# rj45-breakout-10_5_0.net
KiCad netlist of a schematic drawn in EAGLE
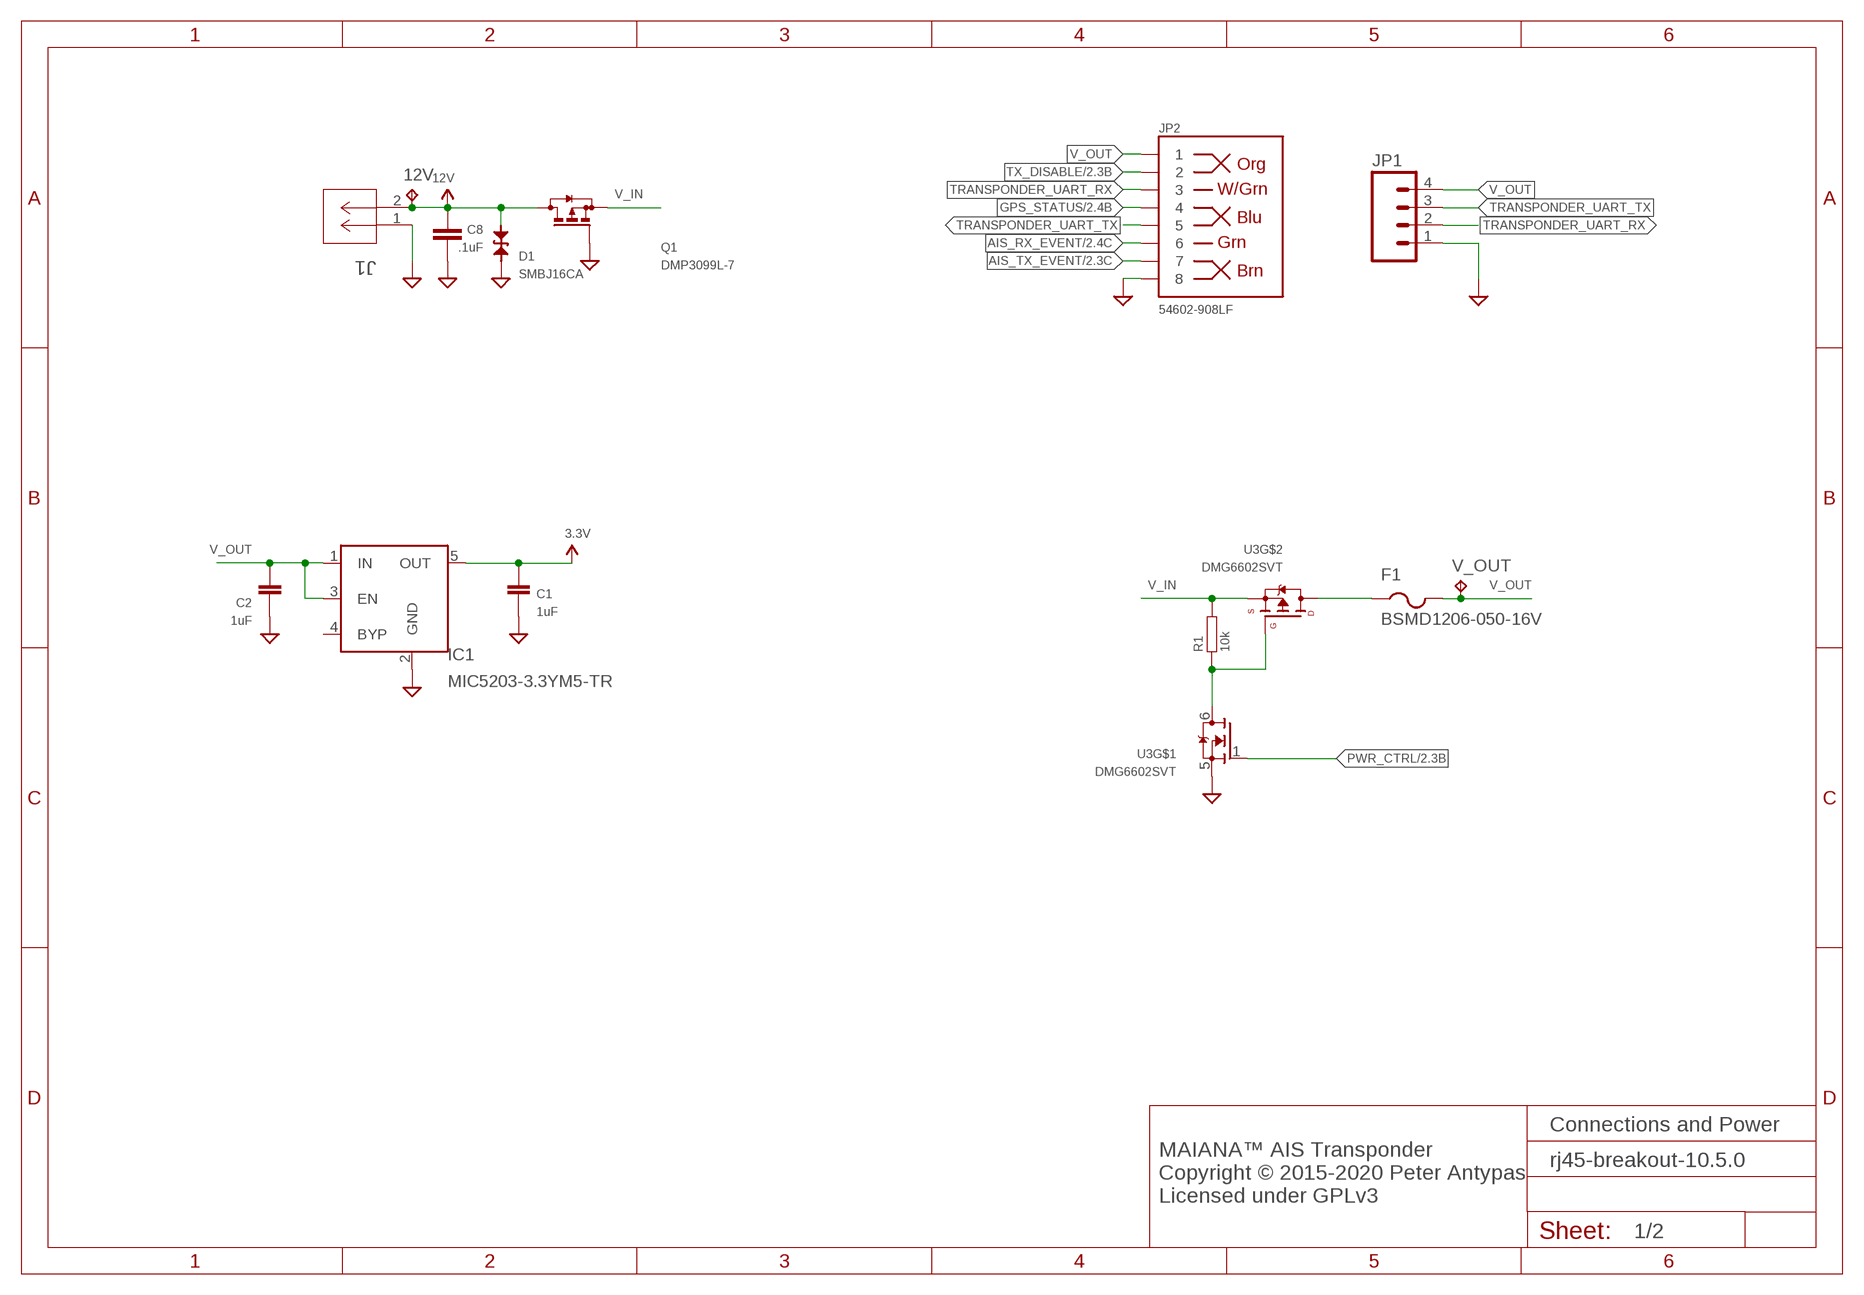
[diagram p0: schematic, sheet 1]
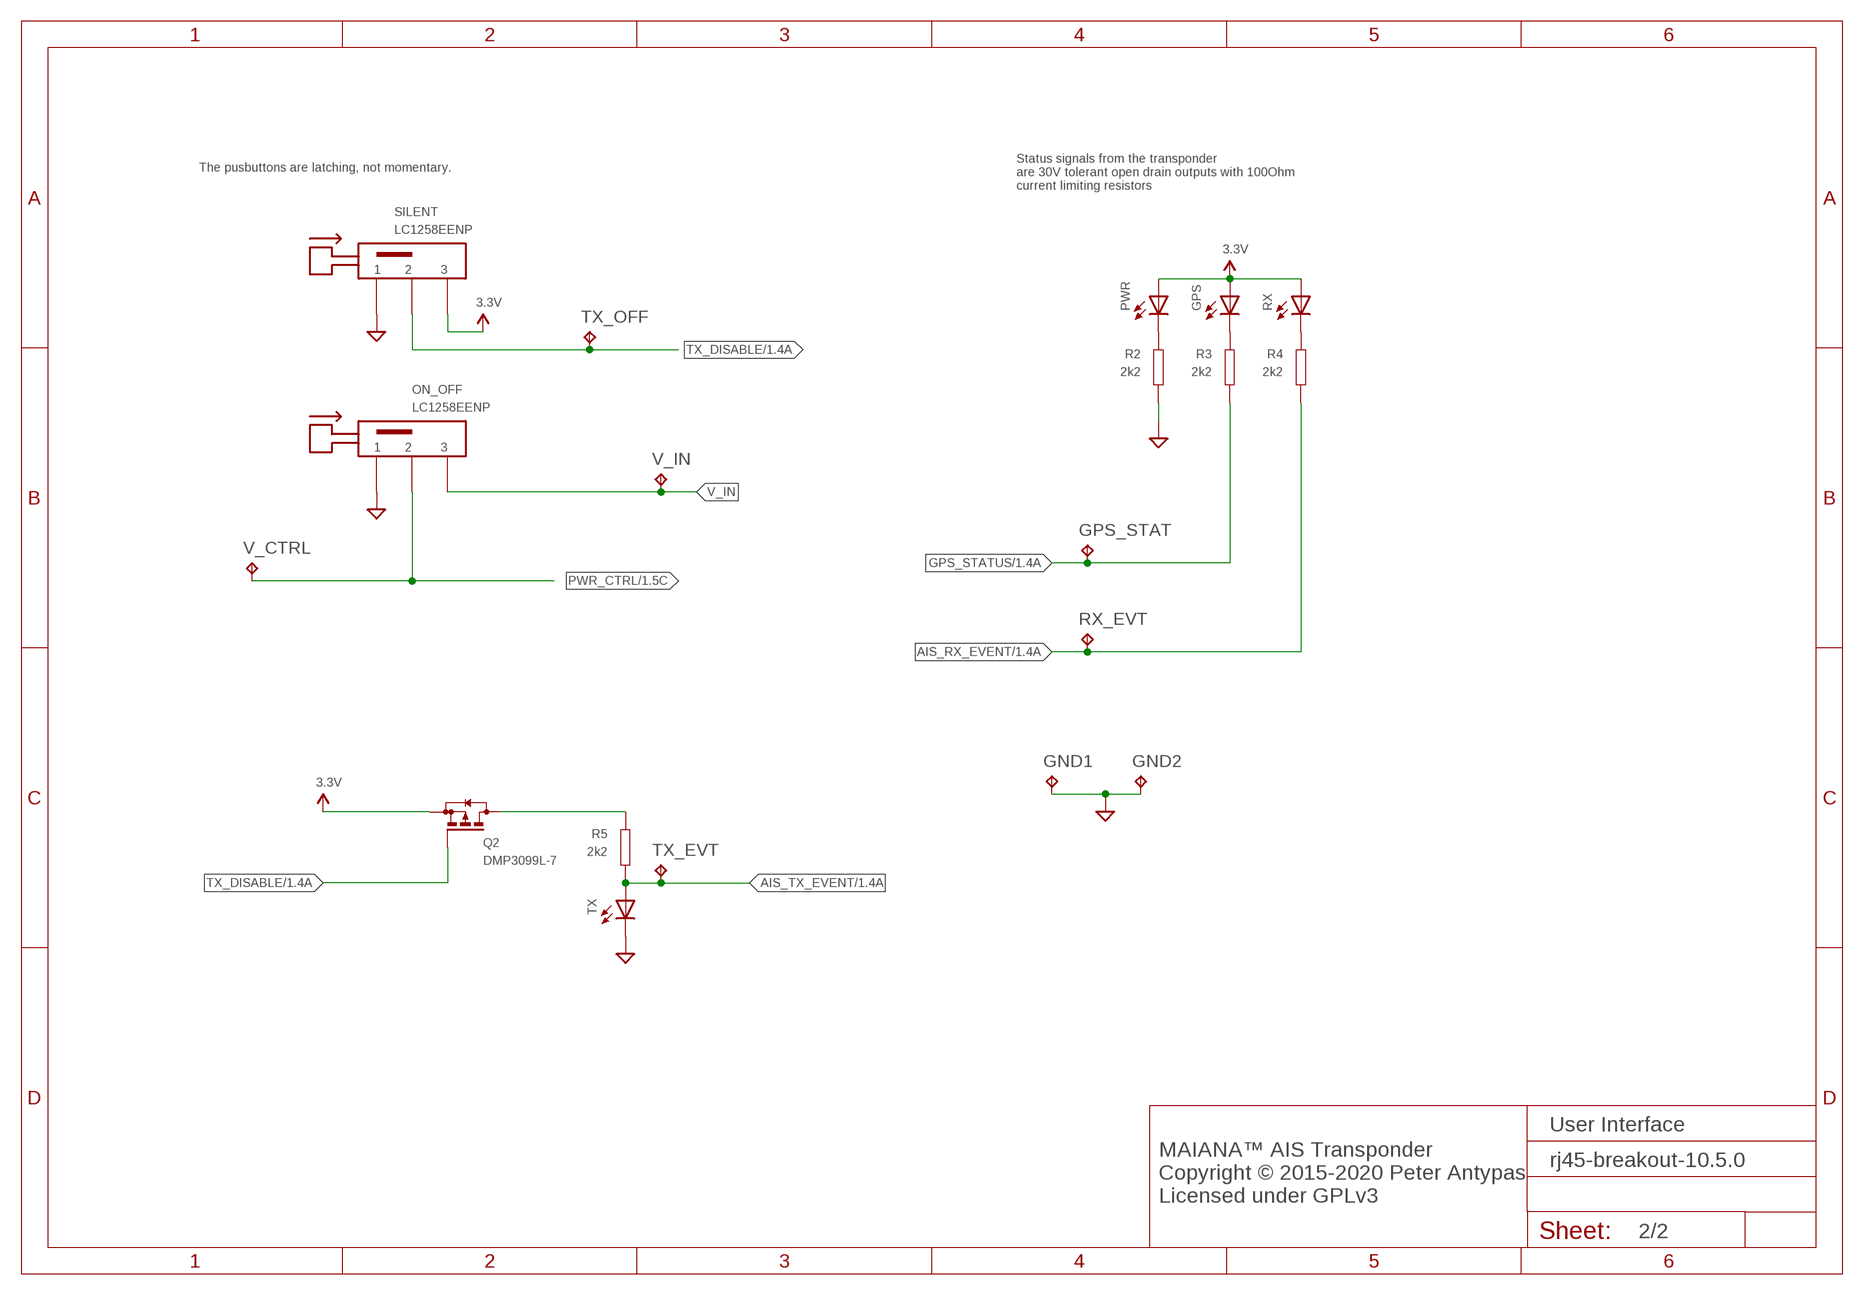
[diagram p1: schematic, sheet 2]

(export (version "E")
  (design (tool "Eeschema 10.0.6"))
  (components
    (comp (ref "GND1")
      (value "TPTP20R")
      (footprint "eagle-import:TP20R")
      (libsource (lib "eagle-import") (part "TPTP20R"))
    )
    (comp (ref "GND2")
      (value "TPTP20R")
      (footprint "eagle-import:TP20R")
      (libsource (lib "eagle-import") (part "TPTP20R"))
    )
    (comp (ref "GPS")
      (value "LEDCHIPLED_1206")
      (footprint "eagle-import:CHIPLED_1206")
      (libsource (lib "eagle-import") (part "LEDCHIPLED_1206"))
    )
    (comp (ref "GPS_STAT")
      (value "TPTP20R")
      (footprint "eagle-import:TP20R")
      (libsource (lib "eagle-import") (part "TPTP20R"))
    )
    (comp (ref "ON_OFF")
      (value "LC1258EENP")
      (footprint "eagle-import:LC1258XXNP")
      (libsource (lib "eagle-import") (part "LC1258XXNP"))
    )
    (comp (ref "PWR")
      (value "LEDCHIPLED_1206")
      (footprint "eagle-import:CHIPLED_1206")
      (libsource (lib "eagle-import") (part "LEDCHIPLED_1206"))
    )
    (comp (ref "Q2")
      (value "DMP3099L-7")
      (footprint "eagle-import:SOT23")
      (libsource (lib "eagle-import") (part "BSS84"))
    )
    (comp (ref "R2")
      (value "2k2")
      (footprint "eagle-import:0603")
      (libsource (lib "eagle-import") (part "RESISTOR0603"))
    )
    (comp (ref "R3")
      (value "2k2")
      (footprint "eagle-import:0603")
      (libsource (lib "eagle-import") (part "RESISTOR0603"))
    )
    (comp (ref "R4")
      (value "2k2")
      (footprint "eagle-import:0603")
      (libsource (lib "eagle-import") (part "RESISTOR0603"))
    )
    (comp (ref "R5")
      (value "2k2")
      (footprint "eagle-import:0603")
      (libsource (lib "eagle-import") (part "RESISTOR0603"))
    )
    (comp (ref "RX")
      (value "LEDCHIPLED_1206")
      (footprint "eagle-import:CHIPLED_1206")
      (libsource (lib "eagle-import") (part "LEDCHIPLED_1206"))
    )
    (comp (ref "RX_EVT")
      (value "TPTP20R")
      (footprint "eagle-import:TP20R")
      (libsource (lib "eagle-import") (part "TPTP20R"))
    )
    (comp (ref "SILENT")
      (value "LC1258EENP")
      (footprint "eagle-import:LC1258XXNP")
      (libsource (lib "eagle-import") (part "LC1258XXNP"))
    )
    (comp (ref "TX")
      (value "LEDCHIPLED_1206")
      (footprint "eagle-import:CHIPLED_1206")
      (libsource (lib "eagle-import") (part "LEDCHIPLED_1206"))
    )
    (comp (ref "TX_EVT")
      (value "TPTP20R")
      (footprint "eagle-import:TP20R")
      (libsource (lib "eagle-import") (part "TPTP20R"))
    )
    (comp (ref "TX_OFF")
      (value "TPTP20R")
      (footprint "eagle-import:TP20R")
      (libsource (lib "eagle-import") (part "TPTP20R"))
    )
    (comp (ref "V_CTRL")
      (value "TPTP20R")
      (footprint "eagle-import:TP20R")
      (libsource (lib "eagle-import") (part "TPTP20R"))
    )
    (comp (ref "V_IN")
      (value "TPTP20R")
      (footprint "eagle-import:TP20R")
      (libsource (lib "eagle-import") (part "TPTP20R"))
    )
    (comp (ref "12V")
      (value "TPTP20R")
      (footprint "eagle-import:TP20R")
      (libsource (lib "eagle-import") (part "TPTP20R"))
    )
    (comp (ref "C1")
      (value "1uF")
      (footprint "eagle-import:0603")
      (libsource (lib "eagle-import") (part "CAPACITOR0603"))
    )
    (comp (ref "C2")
      (value "1uF")
      (footprint "eagle-import:0603")
      (libsource (lib "eagle-import") (part "CAPACITOR0603"))
    )
    (comp (ref "C8")
      (value ".1uF")
      (footprint "eagle-import:0603-CAP")
      (fields (field (name "PARTNO") "GRM188R71E223KA01D"))
      (libsource (lib "eagle-import") (part "CAP0603-CAP"))
    )
    (comp (ref "D1")
      (value "SMBJ16CA")
      (footprint "eagle-import:SMB-BIDIR")
      (libsource (lib "eagle-import") (part "DIODE-TVS-BIDIRSMB"))
    )
    (comp (ref "F1")
      (value "BSMD1206-050-16V")
      (footprint "eagle-import:R1206")
      (libsource (lib "eagle-import") (part "PTCFUSE-1206"))
    )
    (comp (ref "IC1")
      (value "MIC5203-3.3YM5-TR")
      (footprint "eagle-import:SOT23-5")
      (libsource (lib "eagle-import") (part "MIC5219XX"))
    )
    (comp (ref "J1")
      (value "OSTVN02A150")
      (footprint "eagle-import:CONN_OSTVN02A150_OST")
      (fields (field (name "COPYRIGHT") "Copyright (C) 2018 Accelerated Designs. All rights reserved"))
      (libsource (lib "eagle-import") (part "OSTVN02A150"))
    )
    (comp (ref "JP1")
      (value "M04PTH")
      (footprint "eagle-import:1X04")
      (libsource (lib "eagle-import") (part "M04PTH"))
    )
    (comp (ref "JP2")
      (value "54602-908LF")
      (footprint "eagle-import:RJ45-8")
      (libsource (lib "eagle-import") (part "RJ45-8PTH"))
    )
    (comp (ref "Q1")
      (value "DMP3099L-7")
      (footprint "eagle-import:SOT23")
      (libsource (lib "eagle-import") (part "BSS84"))
    )
    (comp (ref "R1")
      (value "10k")
      (footprint "eagle-import:0603")
      (libsource (lib "eagle-import") (part "RESISTOR0603"))
    )
    (comp (ref "U3")
      (value "DMG6602SVT")
      (footprint "eagle-import:SOT23-6")
      (libsource (lib "eagle-import") (part "DMG6602SVT"))
    )
    (comp (ref "V_OUT")
      (value "TPTP20R")
      (footprint "eagle-import:TP20R")
      (libsource (lib "eagle-import") (part "TPTP20R"))
    )
  )
  (nets
    (net (code "1") (name "3.3V") (class "Default")
      (node (ref "C1") (pin "P$1") (pinfunction "1_P$1") (pintype "passive"))
      (node (ref "GPS") (pin "A") (pinfunction "A_A") (pintype "passive"))
      (node (ref "IC1") (pin "5") (pinfunction "OUT_5") (pintype "output"))
      (node (ref "PWR") (pin "A") (pinfunction "A_A") (pintype "passive"))
      (node (ref "Q2") (pin "2") (pinfunction "S_2") (pintype "passive"))
      (node (ref "RX") (pin "A") (pinfunction "A_A") (pintype "passive"))
      (node (ref "SILENT") (pin "P$3") (pinfunction "3_P$3") (pintype "bidirectional"))
    )
    (net (code "2") (name "12V") (class "Default")
      (node (ref "12V") (pin "TP") (pinfunction "TP_TP") (pintype "input"))
      (node (ref "C8") (pin "1") (pinfunction "1_1") (pintype "passive"))
      (node (ref "D1") (pin "A") (pinfunction "P$1_A") (pintype "bidirectional"))
      (node (ref "J1") (pin "2") (pinfunction "2_2") (pintype "passive"))
      (node (ref "Q1") (pin "3") (pinfunction "D_3") (pintype "passive"))
    )
    (net (code "3") (name "AIS_RX_EVENT") (class "Default")
      (node (ref "JP2") (pin "6") (pinfunction "6_6") (pintype "bidirectional"))
      (node (ref "R4") (pin "P$2") (pinfunction "P$2_P$2") (pintype "passive"))
      (node (ref "RX_EVT") (pin "TP") (pinfunction "TP_TP") (pintype "input"))
    )
    (net (code "4") (name "AIS_TX_EVENT") (class "Default")
      (node (ref "JP2") (pin "7") (pinfunction "7_7") (pintype "bidirectional"))
      (node (ref "R5") (pin "P$2") (pinfunction "P$2_P$2") (pintype "passive"))
      (node (ref "TX") (pin "A") (pinfunction "A_A") (pintype "passive"))
      (node (ref "TX_EVT") (pin "TP") (pinfunction "TP_TP") (pintype "input"))
    )
    (net (code "5") (name "GND") (class "Default")
      (node (ref "C1") (pin "P$2") (pinfunction "2_P$2") (pintype "passive"))
      (node (ref "C2") (pin "P$2") (pinfunction "2_P$2") (pintype "passive"))
      (node (ref "C8") (pin "2") (pinfunction "2_2") (pintype "passive"))
      (node (ref "D1") (pin "C") (pinfunction "P$2_C") (pintype "bidirectional"))
      (node (ref "GND1") (pin "TP") (pinfunction "TP_TP") (pintype "input"))
      (node (ref "GND2") (pin "TP") (pinfunction "TP_TP") (pintype "input"))
      (node (ref "IC1") (pin "2") (pinfunction "GND_2") (pintype "power_in"))
      (node (ref "J1") (pin "1") (pinfunction "1_1") (pintype "passive"))
      (node (ref "JP1") (pin "1") (pinfunction "1_1") (pintype "passive"))
      (node (ref "JP2") (pin "8") (pinfunction "8_8") (pintype "bidirectional"))
      (node (ref "ON_OFF") (pin "P$1") (pinfunction "1_P$1") (pintype "bidirectional"))
      (node (ref "Q1") (pin "1") (pinfunction "G_1") (pintype "passive"))
      (node (ref "R2") (pin "P$2") (pinfunction "P$2_P$2") (pintype "passive"))
      (node (ref "SILENT") (pin "P$1") (pinfunction "1_P$1") (pintype "bidirectional"))
      (node (ref "TX") (pin "C") (pinfunction "C_C") (pintype "passive"))
      (node (ref "U3") (pin "5") (pinfunction "S_5") (pintype "bidirectional"))
    )
    (net (code "6") (name "GPS_STATUS") (class "Default")
      (node (ref "GPS_STAT") (pin "TP") (pinfunction "TP_TP") (pintype "input"))
      (node (ref "JP2") (pin "4") (pinfunction "4_4") (pintype "bidirectional"))
      (node (ref "R3") (pin "P$2") (pinfunction "P$2_P$2") (pintype "passive"))
    )
    (net (code "7") (name "Net-(GPS-PadC)") (class "Default")
      (node (ref "GPS") (pin "C") (pinfunction "C_C") (pintype "passive"))
      (node (ref "R3") (pin "P$1") (pinfunction "P$1_P$1") (pintype "passive"))
    )
    (net (code "8") (name "Net-(PWR-PadC)") (class "Default")
      (node (ref "PWR") (pin "C") (pinfunction "C_C") (pintype "passive"))
      (node (ref "R2") (pin "P$1") (pinfunction "P$1_P$1") (pintype "passive"))
    )
    (net (code "9") (name "Net-(Q2-D)") (class "Default")
      (node (ref "Q2") (pin "3") (pinfunction "D_3") (pintype "passive"))
      (node (ref "R5") (pin "P$1") (pinfunction "P$1_P$1") (pintype "passive"))
    )
    (net (code "10") (name "Net-(R4-PadP$1)") (class "Default")
      (node (ref "R4") (pin "P$1") (pinfunction "P$1_P$1") (pintype "passive"))
      (node (ref "RX") (pin "C") (pinfunction "C_C") (pintype "passive"))
    )
    (net (code "11") (name "Net-(U3A-D)") (class "Default")
      (node (ref "R1") (pin "P$1") (pinfunction "P$1_P$1") (pintype "passive"))
      (node (ref "U3") (pin "3") (pinfunction "G_3") (pintype "passive"))
      (node (ref "U3") (pin "6") (pinfunction "D_6") (pintype "bidirectional"))
    )
    (net (code "12") (name "Net-(U3B-D)") (class "Default")
      (node (ref "F1") (pin "1") (pinfunction "1_1") (pintype "passive"))
      (node (ref "U3") (pin "4") (pinfunction "D_4") (pintype "passive"))
    )
    (net (code "13") (name "PWR_CTRL") (class "Default")
      (node (ref "ON_OFF") (pin "P$2") (pinfunction "2_P$2") (pintype "bidirectional"))
      (node (ref "U3") (pin "1") (pinfunction "G_1") (pintype "bidirectional"))
      (node (ref "V_CTRL") (pin "TP") (pinfunction "TP_TP") (pintype "input"))
    )
    (net (code "14") (name "TRANSPONDER_UART_RX") (class "Default")
      (node (ref "JP1") (pin "2") (pinfunction "2_2") (pintype "passive"))
      (node (ref "JP2") (pin "3") (pinfunction "3_3") (pintype "bidirectional"))
    )
    (net (code "15") (name "TRANSPONDER_UART_TX") (class "Default")
      (node (ref "JP1") (pin "3") (pinfunction "3_3") (pintype "passive"))
      (node (ref "JP2") (pin "5") (pinfunction "5_5") (pintype "bidirectional"))
    )
    (net (code "16") (name "TX_DISABLE") (class "Default")
      (node (ref "JP2") (pin "2") (pinfunction "2_2") (pintype "bidirectional"))
      (node (ref "Q2") (pin "1") (pinfunction "G_1") (pintype "passive"))
      (node (ref "SILENT") (pin "P$2") (pinfunction "2_P$2") (pintype "bidirectional"))
      (node (ref "TX_OFF") (pin "TP") (pinfunction "TP_TP") (pintype "input"))
    )
    (net (code "17") (name "V_IN") (class "Default")
      (node (ref "ON_OFF") (pin "P$3") (pinfunction "3_P$3") (pintype "bidirectional"))
      (node (ref "Q1") (pin "2") (pinfunction "S_2") (pintype "passive"))
      (node (ref "R1") (pin "P$2") (pinfunction "P$2_P$2") (pintype "passive"))
      (node (ref "U3") (pin "2") (pinfunction "S_2") (pintype "passive"))
      (node (ref "V_IN") (pin "TP") (pinfunction "TP_TP") (pintype "input"))
    )
    (net (code "18") (name "V_OUT") (class "Default")
      (node (ref "C2") (pin "P$1") (pinfunction "1_P$1") (pintype "passive"))
      (node (ref "F1") (pin "2") (pinfunction "2_2") (pintype "passive"))
      (node (ref "IC1") (pin "1") (pinfunction "IN_1") (pintype "input"))
      (node (ref "IC1") (pin "3") (pinfunction "EN_3") (pintype "input"))
      (node (ref "JP1") (pin "4") (pinfunction "4_4") (pintype "passive"))
      (node (ref "JP2") (pin "1") (pinfunction "1_1") (pintype "bidirectional"))
      (node (ref "V_OUT") (pin "TP") (pinfunction "TP_TP") (pintype "input"))
    )
    (net (code "19") (name "unconnected-(IC1-BYP-Pad4)") (class "Default")
      (node (ref "IC1") (pin "4") (pinfunction "BYP_4") (pintype "passive"))
    )
  )
)
